# Pi_MCU_shield.net
KiCad netlist of a schematic drawn in EAGLE
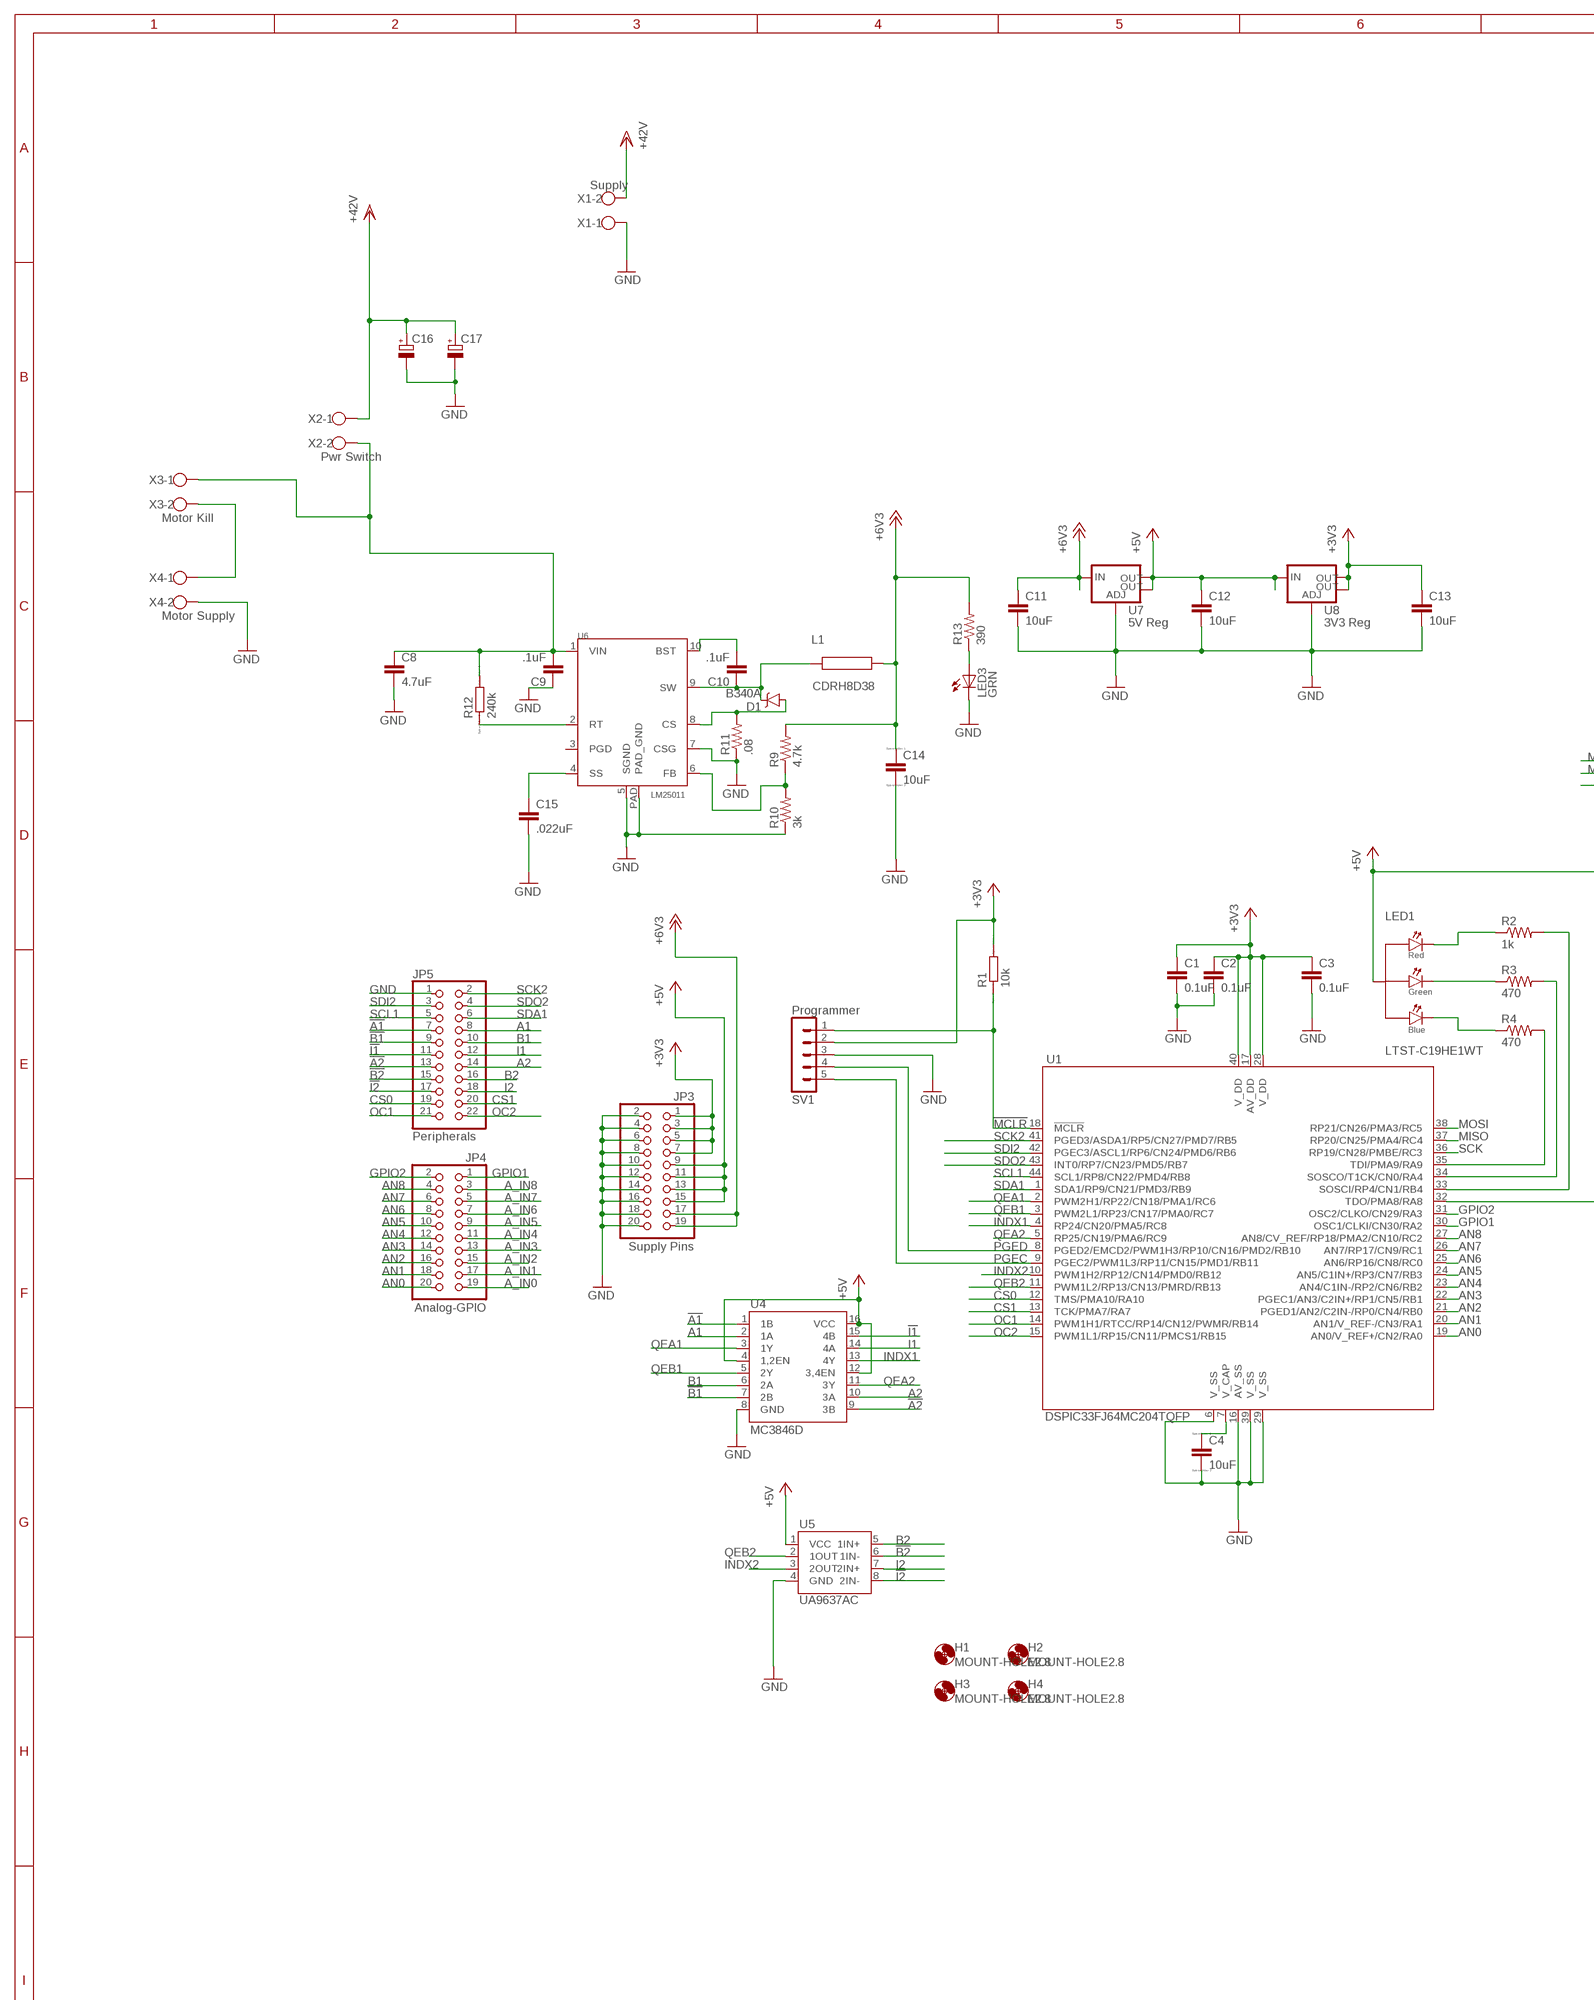
[diagram p0: schematic, sheet 1, part 1 of 2]
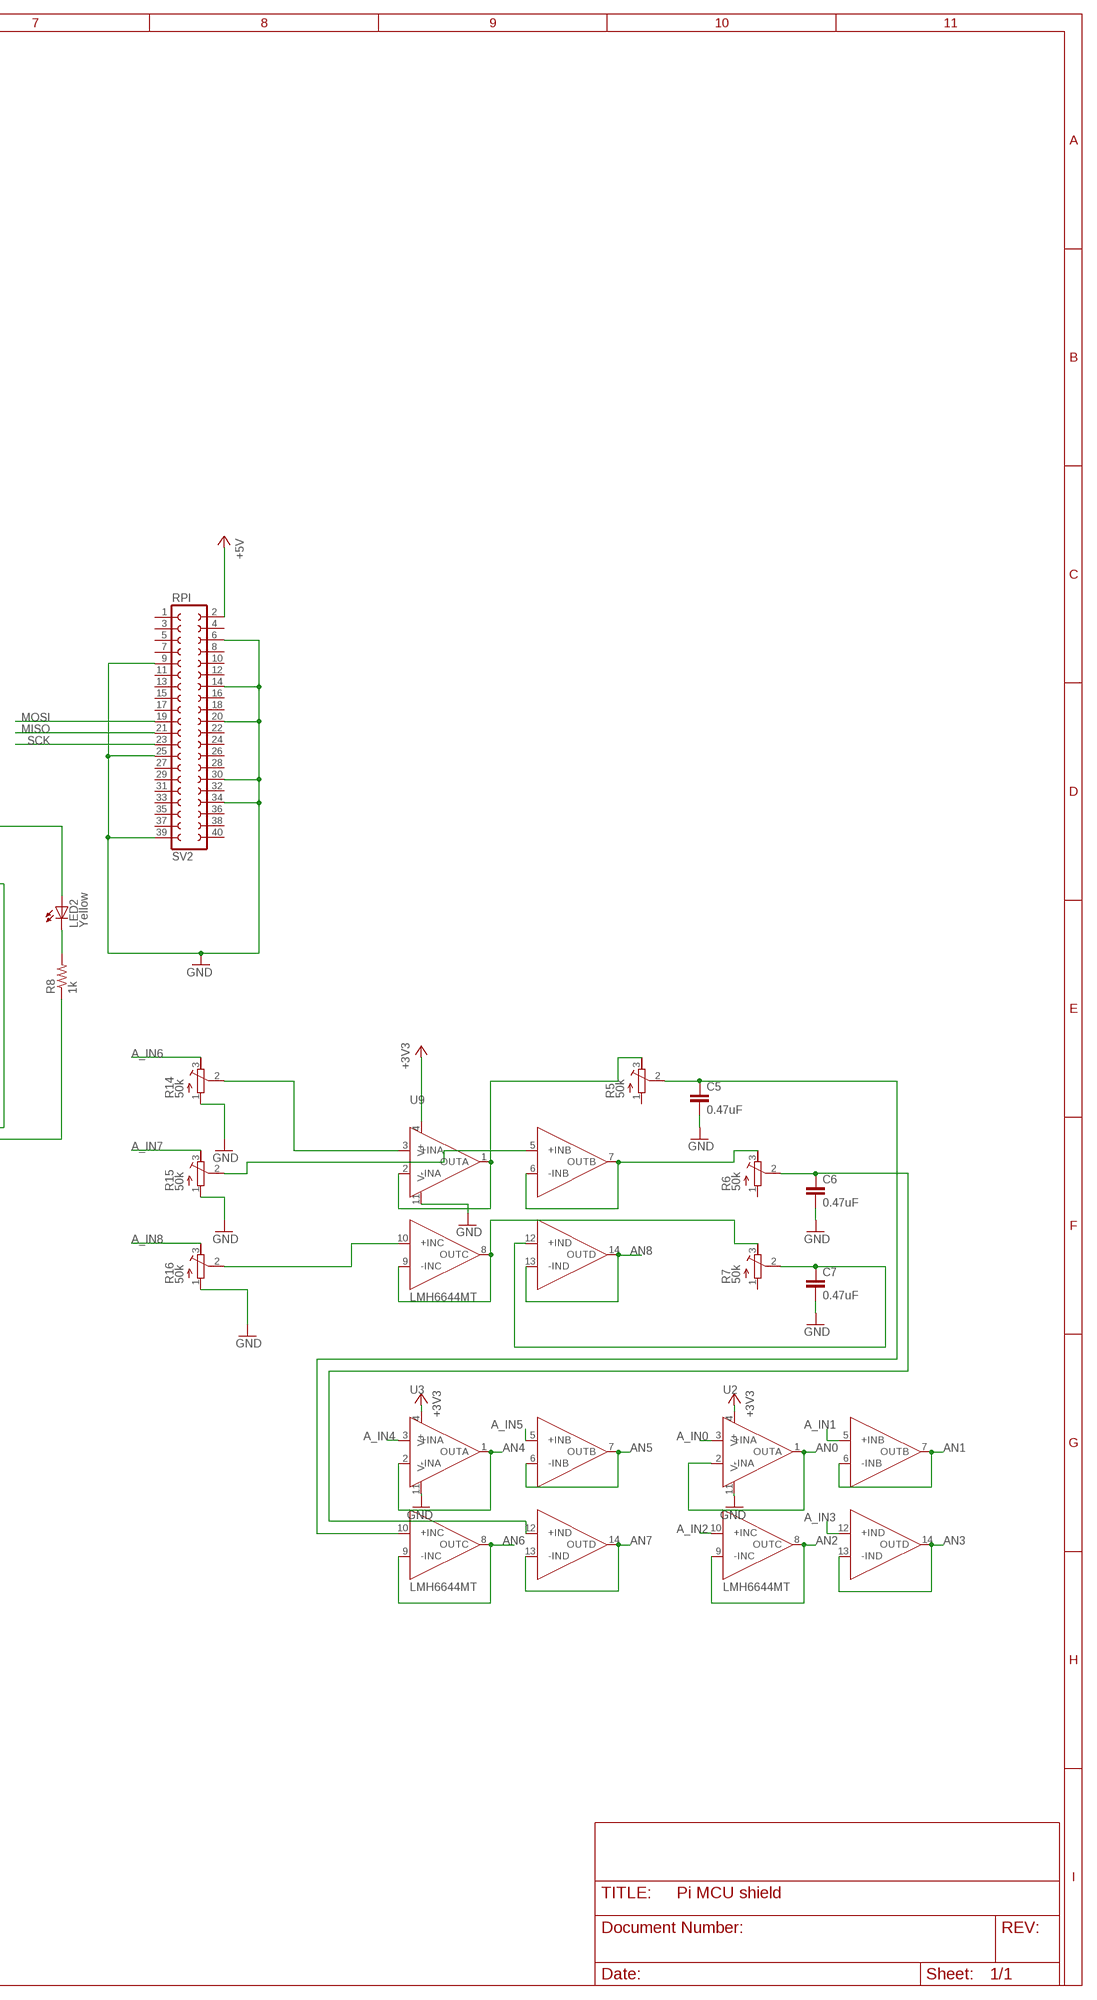
[diagram p1: schematic, sheet 1, part 2 of 2]

(export (version "E")
  (design (tool "Eeschema 10.0.6"))
  (components
    (comp (ref "C1")
      (value "0.1uF")
      (footprint "eagle-import:C0603")
      (libsource (lib "eagle-import") (part "C-EUC0603"))
    )
    (comp (ref "C2")
      (value "0.1uF")
      (footprint "eagle-import:C0603")
      (libsource (lib "eagle-import") (part "C-EUC0603"))
    )
    (comp (ref "C3")
      (value "0.1uF")
      (footprint "eagle-import:C0603")
      (libsource (lib "eagle-import") (part "C-EUC0603"))
    )
    (comp (ref "C4")
      (value "10uF")
      (footprint "eagle-import:C1206")
      (libsource (lib "eagle-import") (part "CC1206"))
    )
    (comp (ref "C5")
      (value "0.47uF")
      (footprint "eagle-import:C0603")
      (libsource (lib "eagle-import") (part "C-EUC0603"))
    )
    (comp (ref "C6")
      (value "0.47uF")
      (footprint "eagle-import:C0603")
      (libsource (lib "eagle-import") (part "C-EUC0603"))
    )
    (comp (ref "C7")
      (value "0.47uF")
      (footprint "eagle-import:C0603")
      (libsource (lib "eagle-import") (part "C-EUC0603"))
    )
    (comp (ref "C8")
      (value "4.7uF")
      (footprint "eagle-import:C1210")
      (libsource (lib "eagle-import") (part "C-EUC1210"))
    )
    (comp (ref "C9")
      (value ".1uF")
      (footprint "eagle-import:0603-CAP")
      (libsource (lib "eagle-import") (part "CAP0603-CAP"))
    )
    (comp (ref "C10")
      (value ".1uF")
      (footprint "eagle-import:0603-CAP")
      (libsource (lib "eagle-import") (part "CAP0603-CAP"))
    )
    (comp (ref "C11")
      (value "10uF")
      (footprint "eagle-import:C0805")
      (libsource (lib "eagle-import") (part "C-EUC0805"))
    )
    (comp (ref "C12")
      (value "10uF")
      (footprint "eagle-import:C0805")
      (libsource (lib "eagle-import") (part "C-EUC0805"))
    )
    (comp (ref "C13")
      (value "10uF")
      (footprint "eagle-import:C0805")
      (libsource (lib "eagle-import") (part "C-EUC0805"))
    )
    (comp (ref "C14")
      (value "10uF")
      (footprint "eagle-import:C1206")
      (libsource (lib "eagle-import") (part "CC1206"))
    )
    (comp (ref "C15")
      (value ".022uF")
      (footprint "eagle-import:0603-CAP")
      (libsource (lib "eagle-import") (part "CAP0603-CAP"))
    )
    (comp (ref "C16")
      (value "CPOL-EUE5-13")
      (footprint "eagle-import:E5-13")
      (libsource (lib "eagle-import") (part "CPOL-EUE5-13"))
    )
    (comp (ref "C17")
      (value "CPOL-EUE5-13")
      (footprint "eagle-import:E5-13")
      (libsource (lib "eagle-import") (part "CPOL-EUE5-13"))
    )
    (comp (ref "D1")
      (value "B340A")
      (footprint "eagle-import:SMA-DIODE")
      (libsource (lib "eagle-import") (part "DIODE-SCHOTTKY-B340A"))
    )
    (comp (ref "H1")
      (value "MOUNT-HOLE2.8")
      (footprint "eagle-import:2,8")
      (libsource (lib "eagle-import") (part "MOUNT-HOLE2.8"))
    )
    (comp (ref "H2")
      (value "MOUNT-HOLE2.8")
      (footprint "eagle-import:2,8")
      (libsource (lib "eagle-import") (part "MOUNT-HOLE2.8"))
    )
    (comp (ref "H3")
      (value "MOUNT-HOLE2.8")
      (footprint "eagle-import:2,8")
      (libsource (lib "eagle-import") (part "MOUNT-HOLE2.8"))
    )
    (comp (ref "H4")
      (value "MOUNT-HOLE2.8")
      (footprint "eagle-import:2,8")
      (libsource (lib "eagle-import") (part "MOUNT-HOLE2.8"))
    )
    (comp (ref "JP3")
      (value "Supply Pins")
      (footprint "eagle-import:2X10")
      (libsource (lib "eagle-import") (part "PINHD-2X10"))
    )
    (comp (ref "JP4")
      (value "Analog-GPIO")
      (footprint "eagle-import:2X10")
      (libsource (lib "eagle-import") (part "PINHD-2X10"))
    )
    (comp (ref "JP5")
      (value "Peripherals")
      (footprint "eagle-import:2X11")
      (libsource (lib "eagle-import") (part "PINHD-2X11"))
    )
    (comp (ref "L1")
      (value "CDRH8D38")
      (footprint "eagle-import:CDRH8D38")
      (libsource (lib "eagle-import") (part "CDRH8D38"))
    )
    (comp (ref "LED1")
      (value "LTST-C19HE1WT")
      (footprint "eagle-import:0606")
      (libsource (lib "eagle-import") (part "LTST-C19HE1WT"))
    )
    (comp (ref "LED2")
      (value "Yellow")
      (footprint "eagle-import:SML0603")
      (libsource (lib "eagle-import") (part "LEDSML0603"))
    )
    (comp (ref "LED3")
      (value "GRN")
      (footprint "eagle-import:CHIP-LED0805")
      (libsource (lib "eagle-import") (part "LEDCHIP-LED0805"))
    )
    (comp (ref "R1")
      (value "10k")
      (footprint "eagle-import:R0805")
      (libsource (lib "eagle-import") (part "R"))
    )
    (comp (ref "R2")
      (value "1k")
      (footprint "eagle-import:R0603")
      (libsource (lib "eagle-import") (part "R-US_R0603"))
    )
    (comp (ref "R3")
      (value "470")
      (footprint "eagle-import:R0603")
      (libsource (lib "eagle-import") (part "R-US_R0603"))
    )
    (comp (ref "R4")
      (value "470")
      (footprint "eagle-import:R0603")
      (libsource (lib "eagle-import") (part "R-US_R0603"))
    )
    (comp (ref "R5")
      (value "50k")
      (footprint "eagle-import:RTRIM3224J")
      (libsource (lib "eagle-import") (part "R-TRIMM3224J"))
    )
    (comp (ref "R6")
      (value "50k")
      (footprint "eagle-import:RTRIM3224J")
      (libsource (lib "eagle-import") (part "R-TRIMM3224J"))
    )
    (comp (ref "R7")
      (value "50k")
      (footprint "eagle-import:RTRIM3224J")
      (libsource (lib "eagle-import") (part "R-TRIMM3224J"))
    )
    (comp (ref "R8")
      (value "1k")
      (footprint "eagle-import:R0603")
      (libsource (lib "eagle-import") (part "R-US_R0603"))
    )
    (comp (ref "R9")
      (value "4.7k")
      (footprint "eagle-import:0603-RES")
      (libsource (lib "eagle-import") (part "RESISTOR0603-RES"))
    )
    (comp (ref "R10")
      (value "3k")
      (footprint "eagle-import:0603-RES")
      (libsource (lib "eagle-import") (part "RESISTOR0603-RES"))
    )
    (comp (ref "R11")
      (value ".08")
      (footprint "eagle-import:0603-RES")
      (libsource (lib "eagle-import") (part "RESISTOR0603-RES"))
    )
    (comp (ref "R12")
      (value "240k")
      (footprint "eagle-import:R0805")
      (libsource (lib "eagle-import") (part "R"))
    )
    (comp (ref "R13")
      (value "390")
      (footprint "eagle-import:0603-RES")
      (libsource (lib "eagle-import") (part "RESISTOR0603-RES"))
    )
    (comp (ref "R14")
      (value "50k")
      (footprint "eagle-import:RTRIM3224J")
      (libsource (lib "eagle-import") (part "R-TRIMM3224J"))
    )
    (comp (ref "R15")
      (value "50k")
      (footprint "eagle-import:RTRIM3224J")
      (libsource (lib "eagle-import") (part "R-TRIMM3224J"))
    )
    (comp (ref "R16")
      (value "50k")
      (footprint "eagle-import:RTRIM3224J")
      (libsource (lib "eagle-import") (part "R-TRIMM3224J"))
    )
    (comp (ref "SV1")
      (value "Programmer")
      (footprint "eagle-import:MA05-1")
      (libsource (lib "eagle-import") (part "MA05-1"))
    )
    (comp (ref "SV2")
      (value "RPI")
      (footprint "eagle-import:FE20-2")
      (libsource (lib "eagle-import") (part "FE20-2"))
    )
    (comp (ref "U1")
      (value "DSPIC33FJ64MC204TQFP")
      (footprint "eagle-import:TQFP44")
      (libsource (lib "eagle-import") (part "DSPIC33FJ64MC204TQFP"))
    )
    (comp (ref "U2")
      (value "LMH6644MT")
      (footprint "eagle-import:TSSOP14")
      (libsource (lib "eagle-import") (part "LMH6644MT"))
    )
    (comp (ref "U3")
      (value "LMH6644MT")
      (footprint "eagle-import:TSSOP14")
      (libsource (lib "eagle-import") (part "LMH6644MT"))
    )
    (comp (ref "U4")
      (value "MC3846D")
      (footprint "eagle-import:SO-16")
      (libsource (lib "eagle-import") (part "MC3846D"))
    )
    (comp (ref "U5")
      (value "UA9637AC")
      (footprint "eagle-import:SO-08")
      (libsource (lib "eagle-import") (part "UA9637AC"))
    )
    (comp (ref "U6")
      (value "LM25011")
      (footprint "eagle-import:HVSS0P-10")
      (libsource (lib "eagle-import") (part "LM25011"))
    )
    (comp (ref "U7")
      (value "5V Reg")
      (footprint "eagle-import:SOT223")
      (libsource (lib "eagle-import") (part "V_REG_LM1117SOT223"))
    )
    (comp (ref "U8")
      (value "3V3 Reg")
      (footprint "eagle-import:SOT223")
      (libsource (lib "eagle-import") (part "V_REG_LM1117SOT223"))
    )
    (comp (ref "U9")
      (value "LMH6644MT")
      (footprint "eagle-import:TSSOP14")
      (libsource (lib "eagle-import") (part "LMH6644MT"))
    )
    (comp (ref "X1")
      (value "Supply")
      (footprint "eagle-import:W237-102")
      (fields (field (name "MPN") "237-102"))
      (libsource (lib "eagle-import") (part "W237-102"))
    )
    (comp (ref "X2")
      (value "Pwr Switch")
      (footprint "eagle-import:W237-102")
      (fields (field (name "MPN") "237-102"))
      (libsource (lib "eagle-import") (part "W237-102"))
    )
    (comp (ref "X3")
      (value "Motor Kill")
      (footprint "eagle-import:W237-102")
      (fields (field (name "MPN") "237-102"))
      (libsource (lib "eagle-import") (part "W237-102"))
    )
    (comp (ref "X4")
      (value "Motor Supply")
      (footprint "eagle-import:W237-102")
      (fields (field (name "MPN") "237-102"))
      (libsource (lib "eagle-import") (part "W237-102"))
    )
  )
  (nets
    (net (code "1") (name "+3V3") (class "Default")
      (node (ref "C1") (pin "1") (pinfunction "1_1") (pintype "passive"))
      (node (ref "C13") (pin "1") (pinfunction "1_1") (pintype "passive"))
      (node (ref "C2") (pin "1") (pinfunction "1_1") (pintype "passive"))
      (node (ref "C3") (pin "1") (pinfunction "1_1") (pintype "passive"))
      (node (ref "JP3") (pin "1") (pinfunction "1_1") (pintype "passive"))
      (node (ref "JP3") (pin "3") (pinfunction "3_3") (pintype "passive"))
      (node (ref "JP3") (pin "5") (pinfunction "5_5") (pintype "passive"))
      (node (ref "JP3") (pin "7") (pinfunction "7_7") (pintype "passive"))
      (node (ref "R1") (pin "2") (pinfunction "2_2") (pintype "passive"))
      (node (ref "SV1") (pin "2") (pinfunction "2_2") (pintype "passive"))
      (node (ref "U1") (pin "17") (pinfunction "AV_DD_17") (pintype "power_in"))
      (node (ref "U1") (pin "28") (pinfunction "V_DD_28") (pintype "power_in"))
      (node (ref "U1") (pin "40") (pinfunction "V_DD_40") (pintype "power_in"))
      (node (ref "U2") (pin "4") (pinfunction "V+_4") (pintype "bidirectional"))
      (node (ref "U3") (pin "4") (pinfunction "V+_4") (pintype "bidirectional"))
      (node (ref "U8") (pin "2") (pinfunction "OUT_2") (pintype "output"))
      (node (ref "U8") (pin "4") (pinfunction "OUT_4") (pintype "output"))
      (node (ref "U9") (pin "4") (pinfunction "V+_4") (pintype "bidirectional"))
    )
    (net (code "2") (name "+5V") (class "Default")
      (node (ref "C12") (pin "1") (pinfunction "1_1") (pintype "passive"))
      (node (ref "JP3") (pin "11") (pinfunction "11_11") (pintype "passive"))
      (node (ref "JP3") (pin "13") (pinfunction "13_13") (pintype "passive"))
      (node (ref "JP3") (pin "15") (pinfunction "15_15") (pintype "passive"))
      (node (ref "JP3") (pin "9") (pinfunction "9_9") (pintype "passive"))
      (node (ref "LED1") (pin "4") (pinfunction "ANODE_4") (pintype "passive"))
      (node (ref "LED2") (pin "A") (pinfunction "A_A") (pintype "passive"))
      (node (ref "SV2") (pin "2") (pinfunction "2_2") (pintype "passive"))
      (node (ref "U4") (pin "12") (pinfunction "3,4EN_12") (pintype "bidirectional"))
      (node (ref "U4") (pin "16") (pinfunction "VCC_16") (pintype "power_in"))
      (node (ref "U4") (pin "4") (pinfunction "1,2EN_4") (pintype "input"))
      (node (ref "U5") (pin "1") (pinfunction "VCC_1") (pintype "power_in"))
      (node (ref "U7") (pin "2") (pinfunction "OUT_2") (pintype "output"))
      (node (ref "U7") (pin "4") (pinfunction "OUT_4") (pintype "output"))
      (node (ref "U8") (pin "3") (pinfunction "IN_3") (pintype "input"))
    )
    (net (code "3") (name "+6V3") (class "Default")
      (node (ref "C11") (pin "1") (pinfunction "1_1") (pintype "passive"))
      (node (ref "C14") (pin "1") (pinfunction "1_1") (pintype "passive"))
      (node (ref "JP3") (pin "17") (pinfunction "17_17") (pintype "passive"))
      (node (ref "JP3") (pin "19") (pinfunction "19_19") (pintype "passive"))
      (node (ref "L1") (pin "P$2") (pinfunction "2_P$2") (pintype "passive"))
      (node (ref "R13") (pin "2") (pinfunction "2_2") (pintype "passive"))
      (node (ref "R9") (pin "2") (pinfunction "2_2") (pintype "passive"))
      (node (ref "U7") (pin "3") (pinfunction "IN_3") (pintype "input"))
    )
    (net (code "4") (name "+42V") (class "Default")
      (node (ref "C16") (pin "+") (pinfunction "+_+") (pintype "passive"))
      (node (ref "C17") (pin "+") (pinfunction "+_+") (pintype "passive"))
      (node (ref "X1") (pin "2") (pinfunction "KL_2") (pintype "passive"))
      (node (ref "X2") (pin "1") (pinfunction "KL_1") (pintype "passive"))
    )
    (net (code "5") (name "/A1") (class "Default")
      (node (ref "JP5") (pin "8") (pinfunction "8_8") (pintype "passive"))
      (node (ref "U4") (pin "2") (pinfunction "1A_2") (pintype "input"))
    )
    (net (code "6") (name "/A2") (class "Default")
      (node (ref "JP5") (pin "14") (pinfunction "14_14") (pintype "passive"))
      (node (ref "U4") (pin "10") (pinfunction "3A_10") (pintype "input"))
    )
    (net (code "7") (name "/AN0") (class "Default")
      (node (ref "JP4") (pin "20") (pinfunction "20_20") (pintype "passive"))
      (node (ref "U1") (pin "19") (pinfunction "AN0/V_REF+/CN2/RA0_19") (pintype "bidirectional"))
      (node (ref "U2") (pin "1") (pinfunction "OUTA_1") (pintype "bidirectional"))
      (node (ref "U2") (pin "2") (pinfunction "-INA_2") (pintype "bidirectional"))
    )
    (net (code "8") (name "/AN1") (class "Default")
      (node (ref "JP4") (pin "18") (pinfunction "18_18") (pintype "passive"))
      (node (ref "U1") (pin "20") (pinfunction "AN1/V_REF-/CN3/RA1_20") (pintype "bidirectional"))
      (node (ref "U2") (pin "6") (pinfunction "-INB_6") (pintype "bidirectional"))
      (node (ref "U2") (pin "7") (pinfunction "OUTB_7") (pintype "bidirectional"))
    )
    (net (code "9") (name "/AN2") (class "Default")
      (node (ref "JP4") (pin "16") (pinfunction "16_16") (pintype "passive"))
      (node (ref "U1") (pin "21") (pinfunction "PGED1/AN2/C2IN-/RP0/CN4/RB0_21") (pintype "bidirectional"))
      (node (ref "U2") (pin "8") (pinfunction "OUTC_8") (pintype "bidirectional"))
      (node (ref "U2") (pin "9") (pinfunction "-INC_9") (pintype "bidirectional"))
    )
    (net (code "10") (name "/AN3") (class "Default")
      (node (ref "JP4") (pin "14") (pinfunction "14_14") (pintype "passive"))
      (node (ref "U1") (pin "22") (pinfunction "PGEC1/AN3/C2IN+/RP1/CN5/RB1_22") (pintype "bidirectional"))
      (node (ref "U2") (pin "13") (pinfunction "-IND_13") (pintype "bidirectional"))
      (node (ref "U2") (pin "14") (pinfunction "OUTD_14") (pintype "bidirectional"))
    )
    (net (code "11") (name "/AN4") (class "Default")
      (node (ref "JP4") (pin "12") (pinfunction "12_12") (pintype "passive"))
      (node (ref "U1") (pin "23") (pinfunction "AN4/C1IN-/RP2/CN6/RB2_23") (pintype "bidirectional"))
      (node (ref "U3") (pin "1") (pinfunction "OUTA_1") (pintype "bidirectional"))
      (node (ref "U3") (pin "2") (pinfunction "-INA_2") (pintype "bidirectional"))
    )
    (net (code "12") (name "/AN5") (class "Default")
      (node (ref "JP4") (pin "10") (pinfunction "10_10") (pintype "passive"))
      (node (ref "U1") (pin "24") (pinfunction "AN5/C1IN+/RP3/CN7/RB3_24") (pintype "bidirectional"))
      (node (ref "U3") (pin "6") (pinfunction "-INB_6") (pintype "bidirectional"))
      (node (ref "U3") (pin "7") (pinfunction "OUTB_7") (pintype "bidirectional"))
    )
    (net (code "13") (name "/AN6") (class "Default")
      (node (ref "JP4") (pin "8") (pinfunction "8_8") (pintype "passive"))
      (node (ref "U1") (pin "25") (pinfunction "AN6/RP16/CN8/RC0_25") (pintype "bidirectional"))
      (node (ref "U3") (pin "8") (pinfunction "OUTC_8") (pintype "bidirectional"))
      (node (ref "U3") (pin "9") (pinfunction "-INC_9") (pintype "bidirectional"))
    )
    (net (code "14") (name "/AN7") (class "Default")
      (node (ref "JP4") (pin "6") (pinfunction "6_6") (pintype "passive"))
      (node (ref "U1") (pin "26") (pinfunction "AN7/RP17/CN9/RC1_26") (pintype "bidirectional"))
      (node (ref "U3") (pin "13") (pinfunction "-IND_13") (pintype "bidirectional"))
      (node (ref "U3") (pin "14") (pinfunction "OUTD_14") (pintype "bidirectional"))
    )
    (net (code "15") (name "/AN8") (class "Default")
      (node (ref "JP4") (pin "4") (pinfunction "4_4") (pintype "passive"))
      (node (ref "U1") (pin "27") (pinfunction "AN8/CV_REF/RP18/PMA2/CN10/RC2_27") (pintype "bidirectional"))
      (node (ref "U9") (pin "13") (pinfunction "-IND_13") (pintype "bidirectional"))
      (node (ref "U9") (pin "14") (pinfunction "OUTD_14") (pintype "bidirectional"))
    )
    (net (code "16") (name "/A_IN0") (class "Default")
      (node (ref "JP4") (pin "19") (pinfunction "19_19") (pintype "passive"))
      (node (ref "U2") (pin "3") (pinfunction "+INA_3") (pintype "bidirectional"))
    )
    (net (code "17") (name "/A_IN1") (class "Default")
      (node (ref "JP4") (pin "17") (pinfunction "17_17") (pintype "passive"))
      (node (ref "U2") (pin "5") (pinfunction "+INB_5") (pintype "bidirectional"))
    )
    (net (code "18") (name "/A_IN2") (class "Default")
      (node (ref "JP4") (pin "15") (pinfunction "15_15") (pintype "passive"))
      (node (ref "U2") (pin "10") (pinfunction "+INC_10") (pintype "bidirectional"))
    )
    (net (code "19") (name "/A_IN3") (class "Default")
      (node (ref "JP4") (pin "13") (pinfunction "13_13") (pintype "passive"))
      (node (ref "U2") (pin "12") (pinfunction "+IND_12") (pintype "bidirectional"))
    )
    (net (code "20") (name "/A_IN4") (class "Default")
      (node (ref "JP4") (pin "11") (pinfunction "11_11") (pintype "passive"))
      (node (ref "U3") (pin "3") (pinfunction "+INA_3") (pintype "bidirectional"))
    )
    (net (code "21") (name "/A_IN5") (class "Default")
      (node (ref "JP4") (pin "9") (pinfunction "9_9") (pintype "passive"))
      (node (ref "U3") (pin "5") (pinfunction "+INB_5") (pintype "bidirectional"))
    )
    (net (code "22") (name "/A_IN6") (class "Default")
      (node (ref "JP4") (pin "7") (pinfunction "7_7") (pintype "passive"))
      (node (ref "R14") (pin "3") (pinfunction "E_3") (pintype "passive"))
    )
    (net (code "23") (name "/A_IN7") (class "Default")
      (node (ref "JP4") (pin "5") (pinfunction "5_5") (pintype "passive"))
      (node (ref "R15") (pin "3") (pinfunction "E_3") (pintype "passive"))
    )
    (net (code "24") (name "/A_IN8") (class "Default")
      (node (ref "JP4") (pin "3") (pinfunction "3_3") (pintype "passive"))
      (node (ref "R16") (pin "3") (pinfunction "E_3") (pintype "passive"))
    )
    (net (code "25") (name "/B1") (class "Default")
      (node (ref "JP5") (pin "10") (pinfunction "10_10") (pintype "passive"))
      (node (ref "U4") (pin "6") (pinfunction "2A_6") (pintype "input"))
    )
    (net (code "26") (name "/B2") (class "Default")
      (node (ref "JP5") (pin "16") (pinfunction "16_16") (pintype "passive"))
      (node (ref "U5") (pin "5") (pinfunction "1IN+_5") (pintype "input"))
    )
    (net (code "27") (name "/CS0") (class "Default")
      (node (ref "JP5") (pin "19") (pinfunction "19_19") (pintype "passive"))
      (node (ref "U1") (pin "12") (pinfunction "TMS/PMA10/RA10_12") (pintype "bidirectional"))
    )
    (net (code "28") (name "/CS1") (class "Default")
      (node (ref "JP5") (pin "20") (pinfunction "20_20") (pintype "passive"))
      (node (ref "U1") (pin "13") (pinfunction "TCK/PMA7/RA7_13") (pintype "bidirectional"))
    )
    (net (code "29") (name "/GPIO1") (class "Default")
      (node (ref "JP4") (pin "1") (pinfunction "1_1") (pintype "passive"))
      (node (ref "U1") (pin "30") (pinfunction "OSC1/CLKI/CN30/RA2_30") (pintype "bidirectional"))
    )
    (net (code "30") (name "/GPIO2") (class "Default")
      (node (ref "JP4") (pin "2") (pinfunction "2_2") (pintype "passive"))
      (node (ref "U1") (pin "31") (pinfunction "OSC2/CLKO/CN29/RA3_31") (pintype "bidirectional"))
    )
    (net (code "31") (name "/I1") (class "Default")
      (node (ref "JP5") (pin "12") (pinfunction "12_12") (pintype "passive"))
      (node (ref "U4") (pin "14") (pinfunction "4A_14") (pintype "input"))
    )
    (net (code "32") (name "/I2") (class "Default")
      (node (ref "JP5") (pin "18") (pinfunction "18_18") (pintype "passive"))
      (node (ref "U5") (pin "7") (pinfunction "2IN+_7") (pintype "input"))
    )
    (net (code "33") (name "/INDX1") (class "Default")
      (node (ref "U1") (pin "4") (pinfunction "RP24/CN20/PMA5/RC8_4") (pintype "bidirectional"))
      (node (ref "U4") (pin "13") (pinfunction "4Y_13") (pintype "output"))
    )
    (net (code "34") (name "/INDX2") (class "Default")
      (node (ref "U1") (pin "10") (pinfunction "PWM1H2/RP12/CN14/PMD0/RB12_10") (pintype "bidirectional"))
      (node (ref "U5") (pin "3") (pinfunction "2OUT_3") (pintype "output"))
    )
    (net (code "35") (name "/MISO") (class "Default")
      (node (ref "SV2") (pin "21") (pinfunction "21_21") (pintype "passive"))
      (node (ref "U1") (pin "37") (pinfunction "RP20/CN25/PMA4/RC4_37") (pintype "bidirectional"))
    )
    (net (code "36") (name "/MOSI") (class "Default")
      (node (ref "SV2") (pin "19") (pinfunction "19_19") (pintype "passive"))
      (node (ref "U1") (pin "38") (pinfunction "RP21/CN26/PMA3/RC5_38") (pintype "bidirectional"))
    )
    (net (code "37") (name "/OC1") (class "Default")
      (node (ref "JP5") (pin "21") (pinfunction "21_21") (pintype "passive"))
      (node (ref "U1") (pin "14") (pinfunction "PWM1H1/RTCC/RP14/CN12/PWMR/RB14_14") (pintype "bidirectional"))
    )
    (net (code "38") (name "/OC2") (class "Default")
      (node (ref "JP5") (pin "22") (pinfunction "22_22") (pintype "passive"))
      (node (ref "U1") (pin "15") (pinfunction "PWM1L1/RP15/CN11/PMCS1/RB15_15") (pintype "bidirectional"))
    )
    (net (code "39") (name "/PGEC") (class "Default")
      (node (ref "SV1") (pin "5") (pinfunction "5_5") (pintype "passive"))
      (node (ref "U1") (pin "9") (pinfunction "PGEC2/PWM1L3/RP11/CN15/PMD1/RB11_9") (pintype "bidirectional"))
    )
    (net (code "40") (name "/PGED") (class "Default")
      (node (ref "SV1") (pin "4") (pinfunction "4_4") (pintype "passive"))
      (node (ref "U1") (pin "8") (pinfunction "PGED2/EMCD2/PWM1H3/RP10/CN16/PMD2/RB10_8") (pintype "bidirectional"))
    )
    (net (code "41") (name "/QEA1") (class "Default")
      (node (ref "U1") (pin "2") (pinfunction "PWM2H1/RP22/CN18/PMA1/RC6_2") (pintype "bidirectional"))
      (node (ref "U4") (pin "3") (pinfunction "1Y_3") (pintype "output"))
    )
    (net (code "42") (name "/QEA2") (class "Default")
      (node (ref "U1") (pin "5") (pinfunction "RP25/CN19/PMA6/RC9_5") (pintype "bidirectional"))
      (node (ref "U4") (pin "11") (pinfunction "3Y_11") (pintype "output"))
    )
    (net (code "43") (name "/QEB1") (class "Default")
      (node (ref "U1") (pin "3") (pinfunction "PWM2L1/RP23/CN17/PMA0/RC7_3") (pintype "bidirectional"))
      (node (ref "U4") (pin "5") (pinfunction "2Y_5") (pintype "output"))
    )
    (net (code "44") (name "/QEB2") (class "Default")
      (node (ref "U1") (pin "11") (pinfunction "PWM1L2/RP13/CN13/PMRD/RB13_11") (pintype "bidirectional"))
      (node (ref "U5") (pin "2") (pinfunction "1OUT_2") (pintype "output"))
    )
    (net (code "45") (name "/SCK") (class "Default")
      (node (ref "SV2") (pin "23") (pinfunction "23_23") (pintype "passive"))
      (node (ref "U1") (pin "36") (pinfunction "RP19/CN28/PMBE/RC3_36") (pintype "bidirectional"))
    )
    (net (code "46") (name "/SCK2") (class "Default")
      (node (ref "JP5") (pin "2") (pinfunction "2_2") (pintype "passive"))
      (node (ref "U1") (pin "41") (pinfunction "PGED3/ASDA1/RP5/CN27/PMD7/RB5_41") (pintype "bidirectional"))
    )
    (net (code "47") (name "/SCL1") (class "Default")
      (node (ref "JP5") (pin "5") (pinfunction "5_5") (pintype "passive"))
      (node (ref "U1") (pin "44") (pinfunction "SCL1/RP8/CN22/PMD4/RB8_44") (pintype "bidirectional"))
    )
    (net (code "48") (name "/SDA1") (class "Default")
      (node (ref "JP5") (pin "6") (pinfunction "6_6") (pintype "passive"))
      (node (ref "U1") (pin "1") (pinfunction "SDA1/RP9/CN21/PMD3/RB9_1") (pintype "bidirectional"))
    )
    (net (code "49") (name "/SDI2") (class "Default")
      (node (ref "JP5") (pin "3") (pinfunction "3_3") (pintype "passive"))
      (node (ref "U1") (pin "42") (pinfunction "PGEC3/ASCL1/RP6/CN24/PMD6/RB6_42") (pintype "bidirectional"))
    )
    (net (code "50") (name "/SDO2") (class "Default")
      (node (ref "JP5") (pin "4") (pinfunction "4_4") (pintype "passive"))
      (node (ref "U1") (pin "43") (pinfunction "INT0/RP7/CN23/PMD5/RB7_43") (pintype "bidirectional"))
    )
    (net (code "51") (name "/~{A1}") (class "Default")
      (node (ref "JP5") (pin "7") (pinfunction "7_7") (pintype "passive"))
      (node (ref "U4") (pin "1") (pinfunction "1B_1") (pintype "input"))
    )
    (net (code "52") (name "/~{A2}") (class "Default")
      (node (ref "JP5") (pin "13") (pinfunction "13_13") (pintype "passive"))
      (node (ref "U4") (pin "9") (pinfunction "3B_9") (pintype "input"))
    )
    (net (code "53") (name "/~{B1}") (class "Default")
      (node (ref "JP5") (pin "9") (pinfunction "9_9") (pintype "passive"))
      (node (ref "U4") (pin "7") (pinfunction "2B_7") (pintype "input"))
    )
    (net (code "54") (name "/~{B2}") (class "Default")
      (node (ref "JP5") (pin "15") (pinfunction "15_15") (pintype "passive"))
      (node (ref "U5") (pin "6") (pinfunction "1IN-_6") (pintype "input"))
    )
    (net (code "55") (name "/~{I1}") (class "Default")
      (node (ref "JP5") (pin "11") (pinfunction "11_11") (pintype "passive"))
      (node (ref "U4") (pin "15") (pinfunction "4B_15") (pintype "input"))
    )
    (net (code "56") (name "/~{I2}") (class "Default")
      (node (ref "JP5") (pin "17") (pinfunction "17_17") (pintype "passive"))
      (node (ref "U5") (pin "8") (pinfunction "2IN-_8") (pintype "input"))
    )
    (net (code "57") (name "/~{MCLR}") (class "Default")
      (node (ref "R1") (pin "1") (pinfunction "1_1") (pintype "passive"))
      (node (ref "SV1") (pin "1") (pinfunction "1_1") (pintype "passive"))
      (node (ref "U1") (pin "18") (pinfunction "~{MCLR}_18") (pintype "bidirectional"))
    )
    (net (code "58") (name "GND") (class "Default")
      (node (ref "C1") (pin "2") (pinfunction "2_2") (pintype "passive"))
      (node (ref "C11") (pin "2") (pinfunction "2_2") (pintype "passive"))
      (node (ref "C12") (pin "2") (pinfunction "2_2") (pintype "passive"))
      (node (ref "C13") (pin "2") (pinfunction "2_2") (pintype "passive"))
      (node (ref "C14") (pin "2") (pinfunction "2_2") (pintype "passive"))
      (node (ref "C15") (pin "2") (pinfunction "2_2") (pintype "passive"))
      (node (ref "C16") (pin "-") (pinfunction "-_-") (pintype "passive"))
      (node (ref "C17") (pin "-") (pinfunction "-_-") (pintype "passive"))
      (node (ref "C2") (pin "2") (pinfunction "2_2") (pintype "passive"))
      (node (ref "C3") (pin "2") (pinfunction "2_2") (pintype "passive"))
      (node (ref "C4") (pin "2") (pinfunction "2_2") (pintype "passive"))
      (node (ref "C5") (pin "2") (pinfunction "2_2") (pintype "passive"))
      (node (ref "C6") (pin "2") (pinfunction "2_2") (pintype "passive"))
      (node (ref "C7") (pin "2") (pinfunction "2_2") (pintype "passive"))
      (node (ref "C8") (pin "2") (pinfunction "2_2") (pintype "passive"))
      (node (ref "C9") (pin "1") (pinfunction "1_1") (pintype "passive"))
      (node (ref "JP3") (pin "10") (pinfunction "10_10") (pintype "passive"))
      (node (ref "JP3") (pin "12") (pinfunction "12_12") (pintype "passive"))
      (node (ref "JP3") (pin "14") (pinfunction "14_14") (pintype "passive"))
      (node (ref "JP3") (pin "16") (pinfunction "16_16") (pintype "passive"))
      (node (ref "JP3") (pin "18") (pinfunction "18_18") (pintype "passive"))
      (node (ref "JP3") (pin "2") (pinfunction "2_2") (pintype "passive"))
      (node (ref "JP3") (pin "20") (pinfunction "20_20") (pintype "passive"))
      (node (ref "JP3") (pin "4") (pinfunction "4_4") (pintype "passive"))
      (node (ref "JP3") (pin "6") (pinfunction "6_6") (pintype "passive"))
      (node (ref "JP3") (pin "8") (pinfunction "8_8") (pintype "passive"))
      (node (ref "JP5") (pin "1") (pinfunction "1_1") (pintype "passive"))
      (node (ref "LED3") (pin "C") (pinfunction "C_C") (pintype "passive"))
      (node (ref "R10") (pin "1") (pinfunction "1_1") (pintype "passive"))
      (node (ref "R11") (pin "1") (pinfunction "1_1") (pintype "passive"))
      (node (ref "R14") (pin "1") (pinfunction "A_1") (pintype "passive"))
      (node (ref "R15") (pin "1") (pinfunction "A_1") (pintype "passive"))
      (node (ref "R16") (pin "1") (pinfunction "A_1") (pintype "passive"))
      (node (ref "SV1") (pin "3") (pinfunction "3_3") (pintype "passive"))
      (node (ref "SV2") (pin "14") (pinfunction "14_14") (pintype "passive"))
      (node (ref "SV2") (pin "20") (pinfunction "20_20") (pintype "passive"))
      (node (ref "SV2") (pin "25") (pinfunction "25_25") (pintype "passive"))
      (node (ref "SV2") (pin "30") (pinfunction "30_30") (pintype "passive"))
      (node (ref "SV2") (pin "34") (pinfunction "34_34") (pintype "passive"))
      (node (ref "SV2") (pin "39") (pinfunction "39_39") (pintype "passive"))
      (node (ref "SV2") (pin "6") (pinfunction "6_6") (pintype "passive"))
      (node (ref "SV2") (pin "9") (pinfunction "9_9") (pintype "passive"))
      (node (ref "U1") (pin "16") (pinfunction "AV_SS_16") (pintype "power_in"))
      (node (ref "U1") (pin "29") (pinfunction "V_SS_29") (pintype "power_in"))
      (node (ref "U1") (pin "39") (pinfunction "V_SS_39") (pintype "power_in"))
      (node (ref "U1") (pin "6") (pinfunction "V_SS_6") (pintype "power_in"))
      (node (ref "U2") (pin "11") (pinfunction "V-_11") (pintype "bidirectional"))
      (node (ref "U3") (pin "11") (pinfunction "V-_11") (pintype "bidirectional"))
      (node (ref "U4") (pin "8") (pinfunction "GND_8") (pintype "power_in"))
      (node (ref "U5") (pin "4") (pinfunction "GND_4") (pintype "power_in"))
      (node (ref "U6") (pin "5") (pinfunction "SGND_5") (pintype "bidirectional"))
      (node (ref "U6") (pin "7") (pinfunction "CSG_7") (pintype "bidirectional"))
      (node (ref "U6") (pin "PAD") (pinfunction "PAD_GND_PAD") (pintype "bidirectional"))
      (node (ref "U7") (pin "1") (pinfunction "ADJ_1") (pintype "input"))
      (node (ref "U8") (pin "1") (pinfunction "ADJ_1") (pintype "input"))
      (node (ref "U9") (pin "11") (pinfunction "V-_11") (pintype "bidirectional"))
      (node (ref "X1") (pin "1") (pinfunction "KL_1") (pintype "passive"))
      (node (ref "X4") (pin "2") (pinfunction "KL_2") (pintype "passive"))
    )
    (net (code "59") (name "Net-(L1-1)") (class "Default")
      (node (ref "C10") (pin "1") (pinfunction "1_1") (pintype "passive"))
      (node (ref "D1") (pin "C") (pinfunction "C_C") (pintype "passive"))
      (node (ref "L1") (pin "P$1") (pinfunction "1_P$1") (pintype "passive"))
      (node (ref "U6") (pin "9") (pinfunction "SW_9") (pintype "bidirectional"))
    )
    (net (code "60") (name "Net-(LED1-B_CATHODE)") (class "Default")
      (node (ref "LED1") (pin "3") (pinfunction "B_CATHODE_3") (pintype "passive"))
      (node (ref "R4") (pin "1") (pinfunction "1_1") (pintype "passive"))
    )
    (net (code "61") (name "Net-(LED1-G_CATHODE)") (class "Default")
      (node (ref "LED1") (pin "2") (pinfunction "G_CATHODE_2") (pintype "passive"))
      (node (ref "R3") (pin "1") (pinfunction "1_1") (pintype "passive"))
    )
    (net (code "62") (name "Net-(LED1-R_CATHODE)") (class "Default")
      (node (ref "LED1") (pin "1") (pinfunction "R_CATHODE_1") (pintype "passive"))
      (node (ref "R2") (pin "1") (pinfunction "1_1") (pintype "passive"))
    )
    (net (code "63") (name "Net-(LED2-PadC)") (class "Default")
      (node (ref "LED2") (pin "C") (pinfunction "C_C") (pintype "passive"))
      (node (ref "R8") (pin "2") (pinfunction "2_2") (pintype "passive"))
    )
    (net (code "64") (name "Net-(LED3-PadA)") (class "Default")
      (node (ref "LED3") (pin "A") (pinfunction "A_A") (pintype "passive"))
      (node (ref "R13") (pin "1") (pinfunction "1_1") (pintype "passive"))
    )
    (net (code "65") (name "Net-(R5-E)") (class "Default")
      (node (ref "R5") (pin "3") (pinfunction "E_3") (pintype "passive"))
      (node (ref "U9") (pin "1") (pinfunction "OUTA_1") (pintype "bidirectional"))
      (node (ref "U9") (pin "2") (pinfunction "-INA_2") (pintype "bidirectional"))
    )
    (net (code "66") (name "Net-(R5-S)") (class "Default")
      (node (ref "C5") (pin "1") (pinfunction "1_1") (pintype "passive"))
      (node (ref "R5") (pin "2") (pinfunction "S_2") (pintype "passive"))
      (node (ref "U3") (pin "10") (pinfunction "+INC_10") (pintype "bidirectional"))
    )
    (net (code "67") (name "Net-(R6-E)") (class "Default")
      (node (ref "R6") (pin "3") (pinfunction "E_3") (pintype "passive"))
      (node (ref "U9") (pin "6") (pinfunction "-INB_6") (pintype "bidirectional"))
      (node (ref "U9") (pin "7") (pinfunction "OUTB_7") (pintype "bidirectional"))
    )
    (net (code "68") (name "Net-(R6-S)") (class "Default")
      (node (ref "C6") (pin "1") (pinfunction "1_1") (pintype "passive"))
      (node (ref "R6") (pin "2") (pinfunction "S_2") (pintype "passive"))
      (node (ref "U3") (pin "12") (pinfunction "+IND_12") (pintype "bidirectional"))
    )
    (net (code "69") (name "Net-(R7-E)") (class "Default")
      (node (ref "R7") (pin "3") (pinfunction "E_3") (pintype "passive"))
      (node (ref "U9") (pin "8") (pinfunction "OUTC_8") (pintype "bidirectional"))
      (node (ref "U9") (pin "9") (pinfunction "-INC_9") (pintype "bidirectional"))
    )
    (net (code "70") (name "Net-(R7-S)") (class "Default")
      (node (ref "C7") (pin "1") (pinfunction "1_1") (pintype "passive"))
      (node (ref "R7") (pin "2") (pinfunction "S_2") (pintype "passive"))
      (node (ref "U9") (pin "12") (pinfunction "+IND_12") (pintype "bidirectional"))
    )
    (net (code "71") (name "Net-(R14-S)") (class "Default")
      (node (ref "R14") (pin "2") (pinfunction "S_2") (pintype "passive"))
      (node (ref "U9") (pin "3") (pinfunction "+INA_3") (pintype "bidirectional"))
    )
    (net (code "72") (name "Net-(R15-S)") (class "Default")
      (node (ref "R15") (pin "2") (pinfunction "S_2") (pintype "passive"))
      (node (ref "U9") (pin "5") (pinfunction "+INB_5") (pintype "bidirectional"))
    )
    (net (code "73") (name "Net-(R16-S)") (class "Default")
      (node (ref "R16") (pin "2") (pinfunction "S_2") (pintype "passive"))
      (node (ref "U9") (pin "10") (pinfunction "+INC_10") (pintype "bidirectional"))
    )
    (net (code "74") (name "Net-(U1-SOSCI{slash}RP4{slash}CN1{slash}RB4)") (class "Default")
      (node (ref "R2") (pin "2") (pinfunction "2_2") (pintype "passive"))
      (node (ref "U1") (pin "33") (pinfunction "SOSCI/RP4/CN1/RB4_33") (pintype "bidirectional"))
    )
    (net (code "75") (name "Net-(U1-SOSCO{slash}T1CK{slash}CN0{slash}RA4)") (class "Default")
      (node (ref "R3") (pin "2") (pinfunction "2_2") (pintype "passive"))
      (node (ref "U1") (pin "34") (pinfunction "SOSCO/T1CK/CN0/RA4_34") (pintype "bidirectional"))
    )
    (net (code "76") (name "Net-(U1-TDI{slash}PMA9{slash}RA9)") (class "Default")
      (node (ref "R4") (pin "2") (pinfunction "2_2") (pintype "passive"))
      (node (ref "U1") (pin "35") (pinfunction "TDI/PMA9/RA9_35") (pintype "bidirectional"))
    )
    (net (code "77") (name "Net-(U1-TDO{slash}PMA8{slash}RA8)") (class "Default")
      (node (ref "R8") (pin "1") (pinfunction "1_1") (pintype "passive"))
      (node (ref "U1") (pin "32") (pinfunction "TDO/PMA8/RA8_32") (pintype "bidirectional"))
    )
    (net (code "78") (name "Net-(U1-V_CAP)") (class "Default")
      (node (ref "C4") (pin "1") (pinfunction "1_1") (pintype "passive"))
      (node (ref "U1") (pin "7") (pinfunction "V_CAP_7") (pintype "power_in"))
    )
    (net (code "79") (name "Net-(U6-BST)") (class "Default")
      (node (ref "C10") (pin "2") (pinfunction "2_2") (pintype "passive"))
      (node (ref "U6") (pin "10") (pinfunction "BST_10") (pintype "bidirectional"))
    )
    (net (code "80") (name "Net-(U6-CS)") (class "Default")
      (node (ref "D1") (pin "A") (pinfunction "A_A") (pintype "passive"))
      (node (ref "R11") (pin "2") (pinfunction "2_2") (pintype "passive"))
      (node (ref "U6") (pin "8") (pinfunction "CS_8") (pintype "bidirectional"))
    )
    (net (code "81") (name "Net-(U6-FB)") (class "Default")
      (node (ref "R10") (pin "2") (pinfunction "2_2") (pintype "passive"))
      (node (ref "R9") (pin "1") (pinfunction "1_1") (pintype "passive"))
      (node (ref "U6") (pin "6") (pinfunction "FB_6") (pintype "bidirectional"))
    )
    (net (code "82") (name "Net-(U6-RT)") (class "Default")
      (node (ref "R12") (pin "1") (pinfunction "1_1") (pintype "passive"))
      (node (ref "U6") (pin "2") (pinfunction "RT_2") (pintype "bidirectional"))
    )
    (net (code "83") (name "Net-(U6-SS)") (class "Default")
      (node (ref "C15") (pin "1") (pinfunction "1_1") (pintype "passive"))
      (node (ref "U6") (pin "4") (pinfunction "SS_4") (pintype "bidirectional"))
    )
    (net (code "84") (name "Net-(U6-VIN)") (class "Default")
      (node (ref "C8") (pin "1") (pinfunction "1_1") (pintype "passive"))
      (node (ref "C9") (pin "2") (pinfunction "2_2") (pintype "passive"))
      (node (ref "R12") (pin "2") (pinfunction "2_2") (pintype "passive"))
      (node (ref "U6") (pin "1") (pinfunction "VIN_1") (pintype "bidirectional"))
      (node (ref "X2") (pin "2") (pinfunction "KL_2") (pintype "passive"))
      (node (ref "X3") (pin "1") (pinfunction "KL_1") (pintype "passive"))
    )
    (net (code "85") (name "Net-(X3B-KL)") (class "Default")
      (node (ref "X3") (pin "2") (pinfunction "KL_2") (pintype "passive"))
      (node (ref "X4") (pin "1") (pinfunction "KL_1") (pintype "passive"))
    )
    (net (code "86") (name "unconnected-(R5-A-Pad1)") (class "Default")
      (node (ref "R5") (pin "1") (pinfunction "A_1") (pintype "passive"))
    )
    (net (code "87") (name "unconnected-(R6-A-Pad1)") (class "Default")
      (node (ref "R6") (pin "1") (pinfunction "A_1") (pintype "passive"))
    )
    (net (code "88") (name "unconnected-(R7-A-Pad1)") (class "Default")
      (node (ref "R7") (pin "1") (pinfunction "A_1") (pintype "passive"))
    )
    (net (code "89") (name "unconnected-(SV2-Pad1)") (class "Default")
      (node (ref "SV2") (pin "1") (pinfunction "1_1") (pintype "passive"))
    )
    (net (code "90") (name "unconnected-(SV2-Pad3)") (class "Default")
      (node (ref "SV2") (pin "3") (pinfunction "3_3") (pintype "passive"))
    )
    (net (code "91") (name "unconnected-(SV2-Pad4)") (class "Default")
      (node (ref "SV2") (pin "4") (pinfunction "4_4") (pintype "passive"))
    )
    (net (code "92") (name "unconnected-(SV2-Pad5)") (class "Default")
      (node (ref "SV2") (pin "5") (pinfunction "5_5") (pintype "passive"))
    )
    (net (code "93") (name "unconnected-(SV2-Pad7)") (class "Default")
      (node (ref "SV2") (pin "7") (pinfunction "7_7") (pintype "passive"))
    )
    (net (code "94") (name "unconnected-(SV2-Pad8)") (class "Default")
      (node (ref "SV2") (pin "8") (pinfunction "8_8") (pintype "passive"))
    )
    (net (code "95") (name "unconnected-(SV2-Pad10)") (class "Default")
      (node (ref "SV2") (pin "10") (pinfunction "10_10") (pintype "passive"))
    )
    (net (code "96") (name "unconnected-(SV2-Pad11)") (class "Default")
      (node (ref "SV2") (pin "11") (pinfunction "11_11") (pintype "passive"))
    )
    (net (code "97") (name "unconnected-(SV2-Pad12)") (class "Default")
      (node (ref "SV2") (pin "12") (pinfunction "12_12") (pintype "passive"))
    )
    (net (code "98") (name "unconnected-(SV2-Pad13)") (class "Default")
      (node (ref "SV2") (pin "13") (pinfunction "13_13") (pintype "passive"))
    )
    (net (code "99") (name "unconnected-(SV2-Pad15)") (class "Default")
      (node (ref "SV2") (pin "15") (pinfunction "15_15") (pintype "passive"))
    )
    (net (code "100") (name "unconnected-(SV2-Pad16)") (class "Default")
      (node (ref "SV2") (pin "16") (pinfunction "16_16") (pintype "passive"))
    )
    (net (code "101") (name "unconnected-(SV2-Pad17)") (class "Default")
      (node (ref "SV2") (pin "17") (pinfunction "17_17") (pintype "passive"))
    )
    (net (code "102") (name "unconnected-(SV2-Pad18)") (class "Default")
      (node (ref "SV2") (pin "18") (pinfunction "18_18") (pintype "passive"))
    )
    (net (code "103") (name "unconnected-(SV2-Pad22)") (class "Default")
      (node (ref "SV2") (pin "22") (pinfunction "22_22") (pintype "passive"))
    )
    (net (code "104") (name "unconnected-(SV2-Pad24)") (class "Default")
      (node (ref "SV2") (pin "24") (pinfunction "24_24") (pintype "passive"))
    )
    (net (code "105") (name "unconnected-(SV2-Pad26)") (class "Default")
      (node (ref "SV2") (pin "26") (pinfunction "26_26") (pintype "passive"))
    )
    (net (code "106") (name "unconnected-(SV2-Pad27)") (class "Default")
      (node (ref "SV2") (pin "27") (pinfunction "27_27") (pintype "passive"))
    )
    (net (code "107") (name "unconnected-(SV2-Pad28)") (class "Default")
      (node (ref "SV2") (pin "28") (pinfunction "28_28") (pintype "passive"))
    )
    (net (code "108") (name "unconnected-(SV2-Pad29)") (class "Default")
      (node (ref "SV2") (pin "29") (pinfunction "29_29") (pintype "passive"))
    )
    (net (code "109") (name "unconnected-(SV2-Pad31)") (class "Default")
      (node (ref "SV2") (pin "31") (pinfunction "31_31") (pintype "passive"))
    )
    (net (code "110") (name "unconnected-(SV2-Pad32)") (class "Default")
      (node (ref "SV2") (pin "32") (pinfunction "32_32") (pintype "passive"))
    )
    (net (code "111") (name "unconnected-(SV2-Pad33)") (class "Default")
      (node (ref "SV2") (pin "33") (pinfunction "33_33") (pintype "passive"))
    )
    (net (code "112") (name "unconnected-(SV2-Pad35)") (class "Default")
      (node (ref "SV2") (pin "35") (pinfunction "35_35") (pintype "passive"))
    )
    (net (code "113") (name "unconnected-(SV2-Pad36)") (class "Default")
      (node (ref "SV2") (pin "36") (pinfunction "36_36") (pintype "passive"))
    )
    (net (code "114") (name "unconnected-(SV2-Pad37)") (class "Default")
      (node (ref "SV2") (pin "37") (pinfunction "37_37") (pintype "passive"))
    )
    (net (code "115") (name "unconnected-(SV2-Pad38)") (class "Default")
      (node (ref "SV2") (pin "38") (pinfunction "38_38") (pintype "passive"))
    )
    (net (code "116") (name "unconnected-(SV2-Pad40)") (class "Default")
      (node (ref "SV2") (pin "40") (pinfunction "40_40") (pintype "passive"))
    )
    (net (code "117") (name "unconnected-(U6-PGD-Pad3)") (class "Default")
      (node (ref "U6") (pin "3") (pinfunction "PGD_3") (pintype "bidirectional"))
    )
  )
)
